# headphone.net
KiCad netlist of a schematic drawn in EAGLE
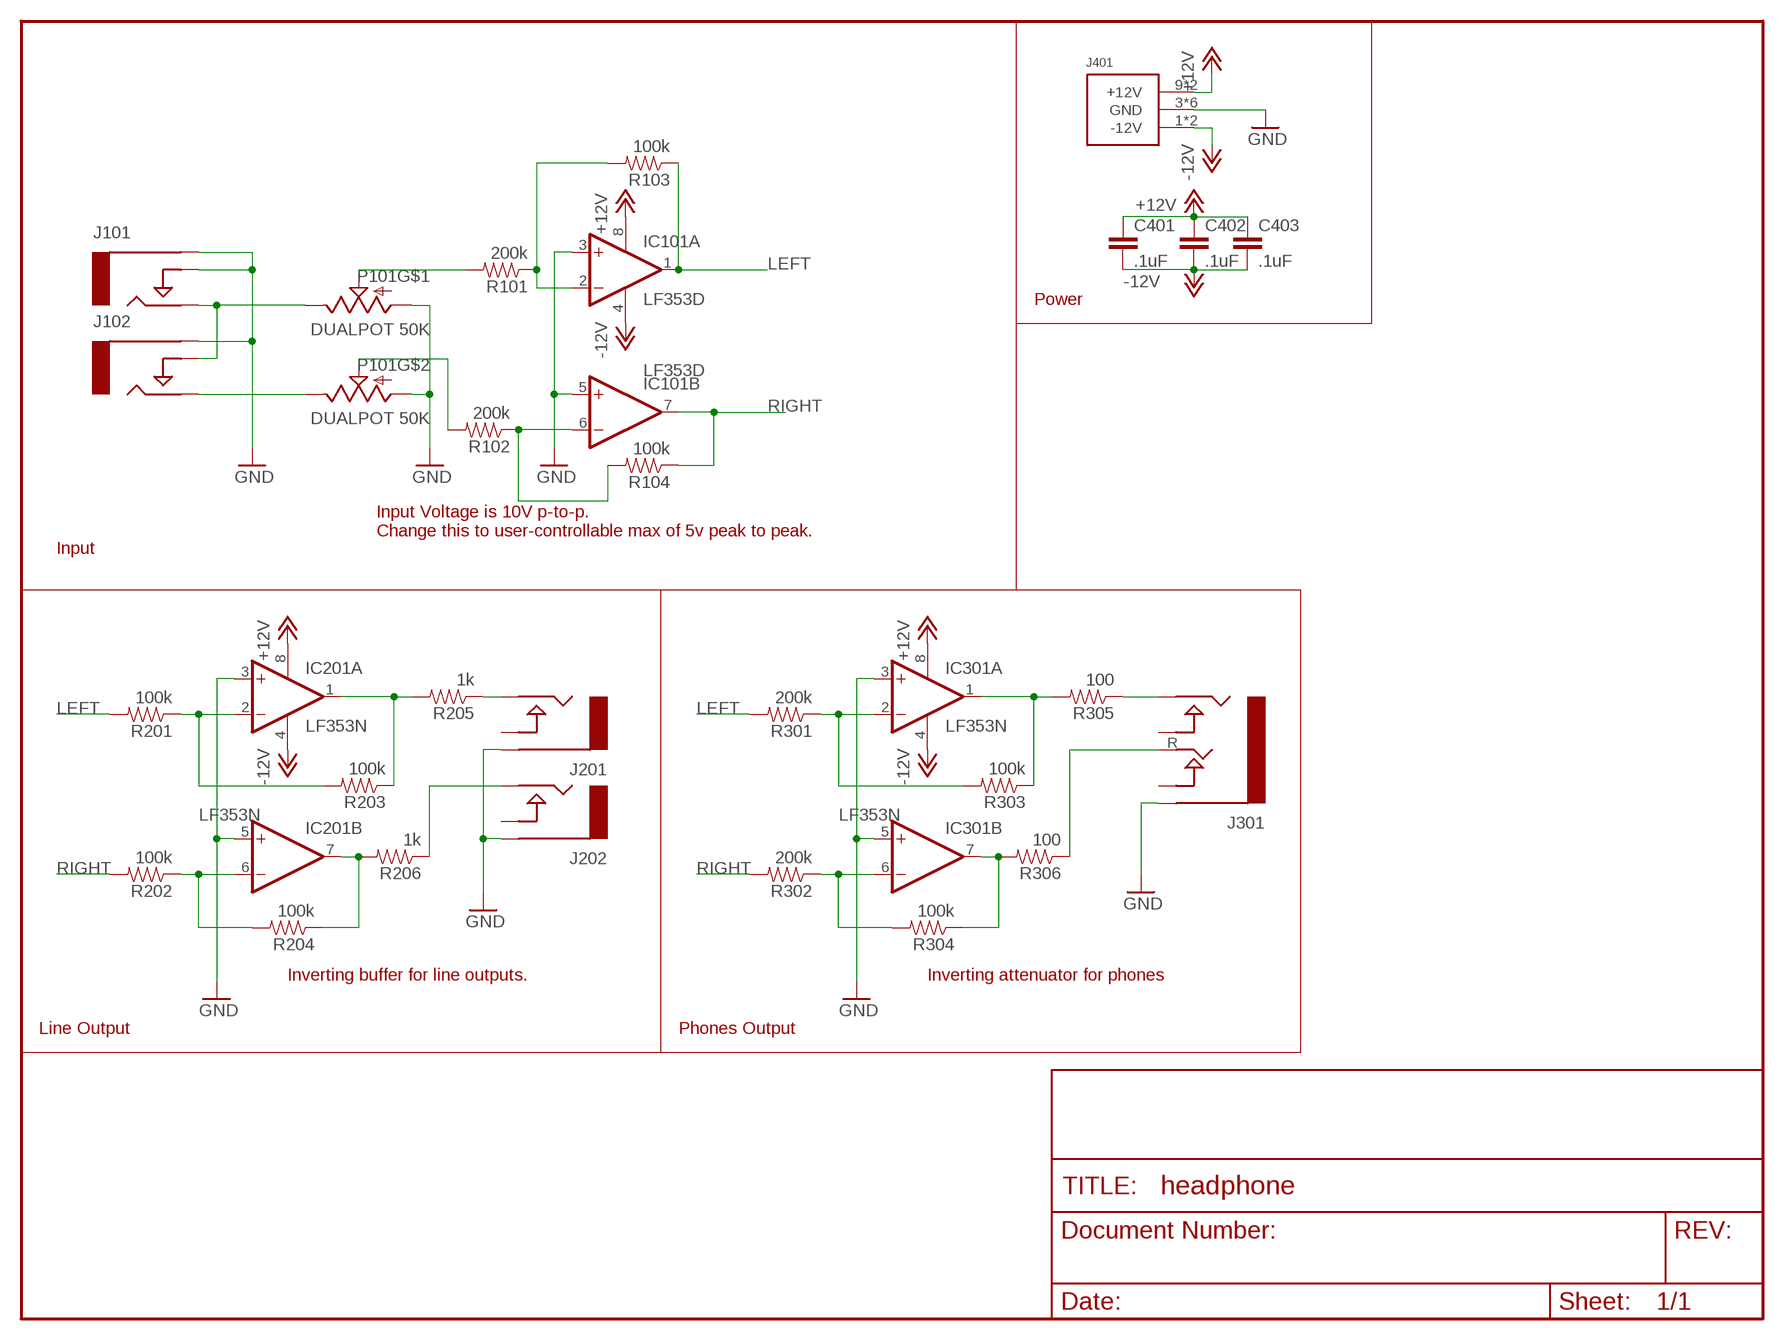
[diagram p0: schematic, sheet 1]

(export (version "E")
  (design (tool "Eeschema 10.0.6"))
  (components
    (comp (ref "C401")
      (value ".1uF")
      (footprint "eagle-import:0603-CAP")
      (libsource (lib "eagle-import") (part "CAP0603-CAP"))
    )
    (comp (ref "C402")
      (value ".1uF")
      (footprint "eagle-import:0603-CAP")
      (libsource (lib "eagle-import") (part "CAP0603-CAP"))
    )
    (comp (ref "C403")
      (value ".1uF")
      (footprint "eagle-import:0603-CAP")
      (libsource (lib "eagle-import") (part "CAP0603-CAP"))
    )
    (comp (ref "IC101")
      (value "LF353D")
      (footprint "eagle-import:SO08")
      (libsource (lib "eagle-import") (part "LF353D"))
    )
    (comp (ref "IC201")
      (value "LF353N")
      (footprint "eagle-import:DIL08")
      (libsource (lib "eagle-import") (part "LF353N"))
    )
    (comp (ref "IC301")
      (value "LF353N")
      (footprint "eagle-import:DIL08")
      (libsource (lib "eagle-import") (part "LF353N"))
    )
    (comp (ref "J101")
      (value "MONOJACKSWITCHCRAFT3")
      (footprint "eagle-import:SWITCHCRAFT_35RAPC2AV")
      (libsource (lib "eagle-import") (part "MONOJACKSWITCHCRAFT3"))
    )
    (comp (ref "J102")
      (value "MONOJACKSWITCHCRAFT3")
      (footprint "eagle-import:SWITCHCRAFT_35RAPC2AV")
      (libsource (lib "eagle-import") (part "MONOJACKSWITCHCRAFT3"))
    )
    (comp (ref "J201")
      (value "MONOJACKNEUTRIK")
      (footprint "eagle-import:NEUTRIK_NMJ4HHD2")
      (libsource (lib "eagle-import") (part "MONOJACKNEUTRIK"))
    )
    (comp (ref "J202")
      (value "MONOJACKNEUTRIK")
      (footprint "eagle-import:NEUTRIK_NMJ4HHD2")
      (libsource (lib "eagle-import") (part "MONOJACKNEUTRIK"))
    )
    (comp (ref "J301")
      (value "STEREOJACK")
      (footprint "eagle-import:NEUTRIK_NMJ6HFD2")
      (libsource (lib "eagle-import") (part "STEREOJACK"))
    )
    (comp (ref "J401")
      (value "POWER_SIMPLE16")
      (footprint "eagle-import:POWER_16")
      (libsource (lib "eagle-import") (part "POWER_SIMPLE16"))
    )
    (comp (ref "P101")
      (value "DUALPOT 50K")
      (footprint "eagle-import:ALPSRK09L12B0A31")
      (libsource (lib "eagle-import") (part "DUALPOT"))
    )
    (comp (ref "R101")
      (value "200k")
      (footprint "eagle-import:0603-RES")
      (libsource (lib "eagle-import") (part "RESISTOR0603-RES"))
    )
    (comp (ref "R102")
      (value "200k")
      (footprint "eagle-import:0603-RES")
      (libsource (lib "eagle-import") (part "RESISTOR0603-RES"))
    )
    (comp (ref "R103")
      (value "100k")
      (footprint "eagle-import:0603-RES")
      (libsource (lib "eagle-import") (part "RESISTOR0603-RES"))
    )
    (comp (ref "R104")
      (value "100k")
      (footprint "eagle-import:0603-RES")
      (libsource (lib "eagle-import") (part "RESISTOR0603-RES"))
    )
    (comp (ref "R201")
      (value "100k")
      (footprint "eagle-import:0603-RES")
      (libsource (lib "eagle-import") (part "RESISTOR0603-RES"))
    )
    (comp (ref "R202")
      (value "100k")
      (footprint "eagle-import:0603-RES")
      (libsource (lib "eagle-import") (part "RESISTOR0603-RES"))
    )
    (comp (ref "R203")
      (value "100k")
      (footprint "eagle-import:0603-RES")
      (libsource (lib "eagle-import") (part "RESISTOR0603-RES"))
    )
    (comp (ref "R204")
      (value "100k")
      (footprint "eagle-import:0603-RES")
      (libsource (lib "eagle-import") (part "RESISTOR0603-RES"))
    )
    (comp (ref "R205")
      (value "1k")
      (footprint "eagle-import:0603-RES")
      (libsource (lib "eagle-import") (part "RESISTOR0603-RES"))
    )
    (comp (ref "R206")
      (value "1k")
      (footprint "eagle-import:0603-RES")
      (libsource (lib "eagle-import") (part "RESISTOR0603-RES"))
    )
    (comp (ref "R301")
      (value "200k")
      (footprint "eagle-import:0603-RES")
      (libsource (lib "eagle-import") (part "RESISTOR0603-RES"))
    )
    (comp (ref "R302")
      (value "200k")
      (footprint "eagle-import:0603-RES")
      (libsource (lib "eagle-import") (part "RESISTOR0603-RES"))
    )
    (comp (ref "R303")
      (value "100k")
      (footprint "eagle-import:0603-RES")
      (libsource (lib "eagle-import") (part "RESISTOR0603-RES"))
    )
    (comp (ref "R304")
      (value "100k")
      (footprint "eagle-import:0603-RES")
      (libsource (lib "eagle-import") (part "RESISTOR0603-RES"))
    )
    (comp (ref "R305")
      (value "100")
      (footprint "eagle-import:0603-RES")
      (libsource (lib "eagle-import") (part "RESISTOR0603-RES"))
    )
    (comp (ref "R306")
      (value "100")
      (footprint "eagle-import:0603-RES")
      (libsource (lib "eagle-import") (part "RESISTOR0603-RES"))
    )
  )
  (nets
    (net (code "1") (name "+12V") (class "Default")
      (node (ref "C401") (pin "1") (pinfunction "1_1") (pintype "passive"))
      (node (ref "C402") (pin "1") (pinfunction "1_1") (pintype "passive"))
      (node (ref "C403") (pin "1") (pinfunction "1_1") (pintype "passive"))
      (node (ref "IC101") (pin "8") (pinfunction "V+_8") (pintype "power_in"))
      (node (ref "IC201") (pin "8") (pinfunction "V+_8") (pintype "power_in"))
      (node (ref "IC301") (pin "8") (pinfunction "V+_8") (pintype "power_in"))
      (node (ref "J401") (pin "10") (pinfunction "+12V_10") (pintype "bidirectional"))
      (node (ref "J401") (pin "9") (pinfunction "+12V_9") (pintype "bidirectional"))
    )
    (net (code "2") (name "-12V") (class "Default")
      (node (ref "C401") (pin "2") (pinfunction "2_2") (pintype "passive"))
      (node (ref "C402") (pin "2") (pinfunction "2_2") (pintype "passive"))
      (node (ref "C403") (pin "2") (pinfunction "2_2") (pintype "passive"))
      (node (ref "IC101") (pin "4") (pinfunction "V-_4") (pintype "power_in"))
      (node (ref "IC201") (pin "4") (pinfunction "V-_4") (pintype "power_in"))
      (node (ref "IC301") (pin "4") (pinfunction "V-_4") (pintype "power_in"))
      (node (ref "J401") (pin "1") (pinfunction "-12V_1") (pintype "bidirectional"))
      (node (ref "J401") (pin "2") (pinfunction "-12V_2") (pintype "bidirectional"))
    )
    (net (code "3") (name "/LEFT") (class "Default")
      (node (ref "IC101") (pin "1") (pinfunction "OUT_1") (pintype "output"))
      (node (ref "R103") (pin "1") (pinfunction "1_1") (pintype "passive"))
      (node (ref "R201") (pin "2") (pinfunction "2_2") (pintype "passive"))
      (node (ref "R301") (pin "2") (pinfunction "2_2") (pintype "passive"))
    )
    (net (code "4") (name "/RIGHT") (class "Default")
      (node (ref "IC101") (pin "7") (pinfunction "OUT_7") (pintype "output"))
      (node (ref "R104") (pin "1") (pinfunction "1_1") (pintype "passive"))
      (node (ref "R202") (pin "2") (pinfunction "2_2") (pintype "passive"))
      (node (ref "R302") (pin "2") (pinfunction "2_2") (pintype "passive"))
    )
    (net (code "5") (name "GND") (class "Default")
      (node (ref "IC101") (pin "3") (pinfunction "+IN_3") (pintype "input"))
      (node (ref "IC101") (pin "5") (pinfunction "+IN_5") (pintype "input"))
      (node (ref "IC201") (pin "3") (pinfunction "+IN_3") (pintype "input"))
      (node (ref "IC201") (pin "5") (pinfunction "+IN_5") (pintype "input"))
      (node (ref "IC301") (pin "3") (pinfunction "+IN_3") (pintype "input"))
      (node (ref "IC301") (pin "5") (pinfunction "+IN_5") (pintype "input"))
      (node (ref "J101") (pin "S") (pinfunction "SLEEVE_S") (pintype "bidirectional"))
      (node (ref "J101") (pin "TN") (pinfunction "NORM_TN") (pintype "bidirectional"))
      (node (ref "J102") (pin "S") (pinfunction "SLEEVE_S") (pintype "bidirectional"))
      (node (ref "J201") (pin "S") (pinfunction "SLEEVE_S") (pintype "bidirectional"))
      (node (ref "J201") (pin "SN") (pinfunction "SLEEVE_SN") (pintype "bidirectional"))
      (node (ref "J202") (pin "S") (pinfunction "SLEEVE_S") (pintype "bidirectional"))
      (node (ref "J202") (pin "SN") (pinfunction "SLEEVE_SN") (pintype "bidirectional"))
      (node (ref "J301") (pin "S") (pinfunction "SLEEVE_S") (pintype "bidirectional"))
      (node (ref "J301") (pin "SN") (pinfunction "SLEEVE_SN") (pintype "bidirectional"))
      (node (ref "J401") (pin "3") (pinfunction "GND_3") (pintype "bidirectional"))
      (node (ref "J401") (pin "4") (pinfunction "GND_4") (pintype "bidirectional"))
      (node (ref "J401") (pin "5") (pinfunction "GND_5") (pintype "bidirectional"))
      (node (ref "J401") (pin "6") (pinfunction "GND_6") (pintype "bidirectional"))
      (node (ref "J401") (pin "7") (pinfunction "GND_7") (pintype "bidirectional"))
      (node (ref "J401") (pin "8") (pinfunction "GND_8") (pintype "bidirectional"))
      (node (ref "P101") (pin "D1") (pinfunction "A_D1") (pintype "passive"))
      (node (ref "P101") (pin "D2") (pinfunction "A_D2") (pintype "passive"))
    )
    (net (code "6") (name "Net-(IC101A--IN)") (class "Default")
      (node (ref "IC101") (pin "2") (pinfunction "-IN_2") (pintype "input"))
      (node (ref "R101") (pin "1") (pinfunction "1_1") (pintype "passive"))
      (node (ref "R103") (pin "2") (pinfunction "2_2") (pintype "passive"))
    )
    (net (code "7") (name "Net-(IC101B--IN)") (class "Default")
      (node (ref "IC101") (pin "6") (pinfunction "-IN_6") (pintype "input"))
      (node (ref "R102") (pin "1") (pinfunction "1_1") (pintype "passive"))
      (node (ref "R104") (pin "2") (pinfunction "2_2") (pintype "passive"))
    )
    (net (code "8") (name "Net-(IC201A--IN)") (class "Default")
      (node (ref "IC201") (pin "2") (pinfunction "-IN_2") (pintype "input"))
      (node (ref "R201") (pin "1") (pinfunction "1_1") (pintype "passive"))
      (node (ref "R203") (pin "2") (pinfunction "2_2") (pintype "passive"))
    )
    (net (code "9") (name "Net-(IC201A-OUT)") (class "Default")
      (node (ref "IC201") (pin "1") (pinfunction "OUT_1") (pintype "output"))
      (node (ref "R203") (pin "1") (pinfunction "1_1") (pintype "passive"))
      (node (ref "R205") (pin "2") (pinfunction "2_2") (pintype "passive"))
    )
    (net (code "10") (name "Net-(IC201B--IN)") (class "Default")
      (node (ref "IC201") (pin "6") (pinfunction "-IN_6") (pintype "input"))
      (node (ref "R202") (pin "1") (pinfunction "1_1") (pintype "passive"))
      (node (ref "R204") (pin "2") (pinfunction "2_2") (pintype "passive"))
    )
    (net (code "11") (name "Net-(IC201B-OUT)") (class "Default")
      (node (ref "IC201") (pin "7") (pinfunction "OUT_7") (pintype "output"))
      (node (ref "R204") (pin "1") (pinfunction "1_1") (pintype "passive"))
      (node (ref "R206") (pin "2") (pinfunction "2_2") (pintype "passive"))
    )
    (net (code "12") (name "Net-(IC301A--IN)") (class "Default")
      (node (ref "IC301") (pin "2") (pinfunction "-IN_2") (pintype "input"))
      (node (ref "R301") (pin "1") (pinfunction "1_1") (pintype "passive"))
      (node (ref "R303") (pin "2") (pinfunction "2_2") (pintype "passive"))
    )
    (net (code "13") (name "Net-(IC301A-OUT)") (class "Default")
      (node (ref "IC301") (pin "1") (pinfunction "OUT_1") (pintype "output"))
      (node (ref "R303") (pin "1") (pinfunction "1_1") (pintype "passive"))
      (node (ref "R305") (pin "2") (pinfunction "2_2") (pintype "passive"))
    )
    (net (code "14") (name "Net-(IC301B--IN)") (class "Default")
      (node (ref "IC301") (pin "6") (pinfunction "-IN_6") (pintype "input"))
      (node (ref "R302") (pin "1") (pinfunction "1_1") (pintype "passive"))
      (node (ref "R304") (pin "2") (pinfunction "2_2") (pintype "passive"))
    )
    (net (code "15") (name "Net-(IC301B-OUT)") (class "Default")
      (node (ref "IC301") (pin "7") (pinfunction "OUT_7") (pintype "output"))
      (node (ref "R304") (pin "1") (pinfunction "1_1") (pintype "passive"))
      (node (ref "R306") (pin "2") (pinfunction "2_2") (pintype "passive"))
    )
    (net (code "16") (name "Net-(J101-TIP)") (class "Default")
      (node (ref "J101") (pin "T") (pinfunction "TIP_T") (pintype "bidirectional"))
      (node (ref "J102") (pin "TN") (pinfunction "NORM_TN") (pintype "bidirectional"))
      (node (ref "P101") (pin "U1") (pinfunction "E_U1") (pintype "passive"))
    )
    (net (code "17") (name "Net-(J102-TIP)") (class "Default")
      (node (ref "J102") (pin "T") (pinfunction "TIP_T") (pintype "bidirectional"))
      (node (ref "P101") (pin "U2") (pinfunction "E_U2") (pintype "passive"))
    )
    (net (code "18") (name "Net-(J201-TIP)") (class "Default")
      (node (ref "J201") (pin "T") (pinfunction "TIP_T") (pintype "bidirectional"))
      (node (ref "R205") (pin "1") (pinfunction "1_1") (pintype "passive"))
    )
    (net (code "19") (name "Net-(J202-TIP)") (class "Default")
      (node (ref "J202") (pin "T") (pinfunction "TIP_T") (pintype "bidirectional"))
      (node (ref "R206") (pin "1") (pinfunction "1_1") (pintype "passive"))
    )
    (net (code "20") (name "Net-(J301-RING)") (class "Default")
      (node (ref "J301") (pin "R") (pinfunction "RING_R") (pintype "bidirectional"))
      (node (ref "R306") (pin "1") (pinfunction "1_1") (pintype "passive"))
    )
    (net (code "21") (name "Net-(J301-TIP)") (class "Default")
      (node (ref "J301") (pin "T") (pinfunction "TIP_T") (pintype "bidirectional"))
      (node (ref "R305") (pin "1") (pinfunction "1_1") (pintype "passive"))
    )
    (net (code "22") (name "Net-(P101A-S)") (class "Default")
      (node (ref "P101") (pin "W1") (pinfunction "S_W1") (pintype "passive"))
      (node (ref "R101") (pin "2") (pinfunction "2_2") (pintype "passive"))
    )
    (net (code "23") (name "Net-(P101B-S)") (class "Default")
      (node (ref "P101") (pin "W2") (pinfunction "S_W2") (pintype "passive"))
      (node (ref "R102") (pin "2") (pinfunction "2_2") (pintype "passive"))
    )
    (net (code "24") (name "unconnected-(J201-NORM-PadTN)") (class "Default")
      (node (ref "J201") (pin "TN") (pinfunction "NORM_TN") (pintype "bidirectional"))
    )
    (net (code "25") (name "unconnected-(J202-NORM-PadTN)") (class "Default")
      (node (ref "J202") (pin "TN") (pinfunction "NORM_TN") (pintype "bidirectional"))
    )
    (net (code "26") (name "unconnected-(J301-NORMRING-PadRN)") (class "Default")
      (node (ref "J301") (pin "RN") (pinfunction "NORMRING_RN") (pintype "bidirectional"))
    )
    (net (code "27") (name "unconnected-(J301-NORMTIP-PadTN)") (class "Default")
      (node (ref "J301") (pin "TN") (pinfunction "NORMTIP_TN") (pintype "bidirectional"))
    )
  )
)
